# 00A-094.net
KiCad netlist of a schematic drawn in EAGLE
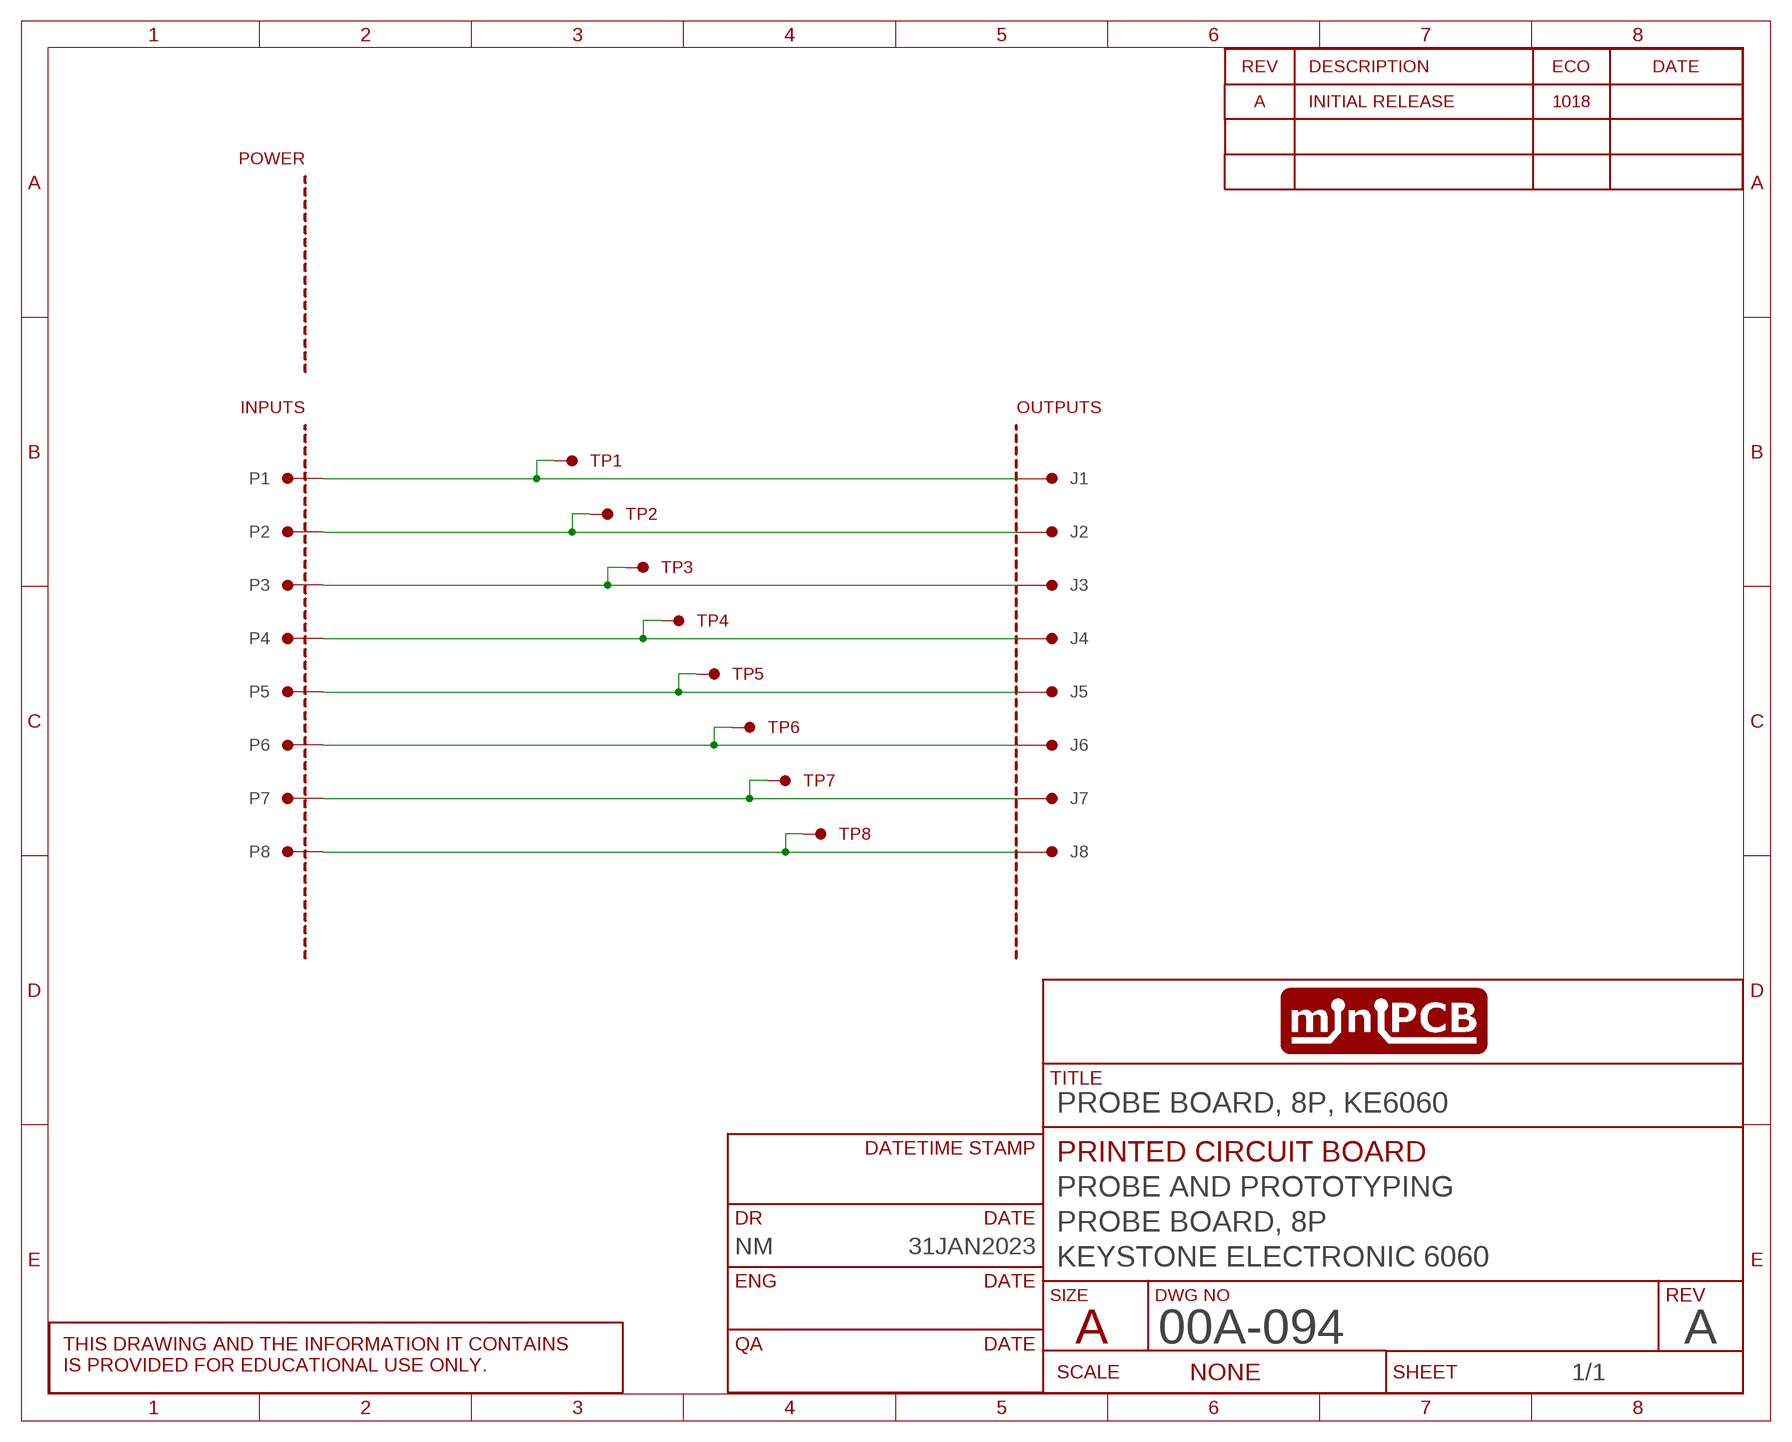
[diagram p0: schematic, sheet 1]

(export (version "E")
  (design (tool "Eeschema 10.0.6"))
  (components
    (comp (ref "J1")
      (value "PINS_1KE6060")
      (footprint "eagle-import:PINS_1_KE6060")
      (libsource (lib "eagle-import") (part "PINS_1KE6060"))
    )
    (comp (ref "J2")
      (value "PINS_1KE6060")
      (footprint "eagle-import:PINS_1_KE6060")
      (libsource (lib "eagle-import") (part "PINS_1KE6060"))
    )
    (comp (ref "J3")
      (value "PINS_1KE6060")
      (footprint "eagle-import:PINS_1_KE6060")
      (libsource (lib "eagle-import") (part "PINS_1KE6060"))
    )
    (comp (ref "J4")
      (value "PINS_1KE6060")
      (footprint "eagle-import:PINS_1_KE6060")
      (libsource (lib "eagle-import") (part "PINS_1KE6060"))
    )
    (comp (ref "J5")
      (value "PINS_1KE6060")
      (footprint "eagle-import:PINS_1_KE6060")
      (libsource (lib "eagle-import") (part "PINS_1KE6060"))
    )
    (comp (ref "J6")
      (value "PINS_1KE6060")
      (footprint "eagle-import:PINS_1_KE6060")
      (libsource (lib "eagle-import") (part "PINS_1KE6060"))
    )
    (comp (ref "J7")
      (value "PINS_1KE6060")
      (footprint "eagle-import:PINS_1_KE6060")
      (libsource (lib "eagle-import") (part "PINS_1KE6060"))
    )
    (comp (ref "J8")
      (value "PINS_1KE6060")
      (footprint "eagle-import:PINS_1_KE6060")
      (libsource (lib "eagle-import") (part "PINS_1KE6060"))
    )
    (comp (ref "P1")
      (value "PINS_124AWG-NOTEXT")
      (footprint "eagle-import:PINS_1_1MM-NOTEXT")
      (libsource (lib "eagle-import") (part "PINS_124AWG-NOTEXT"))
    )
    (comp (ref "P2")
      (value "PINS_124AWG-NOTEXT")
      (footprint "eagle-import:PINS_1_1MM-NOTEXT")
      (libsource (lib "eagle-import") (part "PINS_124AWG-NOTEXT"))
    )
    (comp (ref "P3")
      (value "PINS_124AWG-NOTEXT")
      (footprint "eagle-import:PINS_1_1MM-NOTEXT")
      (libsource (lib "eagle-import") (part "PINS_124AWG-NOTEXT"))
    )
    (comp (ref "P4")
      (value "PINS_124AWG-NOTEXT")
      (footprint "eagle-import:PINS_1_1MM-NOTEXT")
      (libsource (lib "eagle-import") (part "PINS_124AWG-NOTEXT"))
    )
    (comp (ref "P5")
      (value "PINS_124AWG-NOTEXT")
      (footprint "eagle-import:PINS_1_1MM-NOTEXT")
      (libsource (lib "eagle-import") (part "PINS_124AWG-NOTEXT"))
    )
    (comp (ref "P6")
      (value "PINS_124AWG-NOTEXT")
      (footprint "eagle-import:PINS_1_1MM-NOTEXT")
      (libsource (lib "eagle-import") (part "PINS_124AWG-NOTEXT"))
    )
    (comp (ref "P7")
      (value "PINS_124AWG-NOTEXT")
      (footprint "eagle-import:PINS_1_1MM-NOTEXT")
      (libsource (lib "eagle-import") (part "PINS_124AWG-NOTEXT"))
    )
    (comp (ref "P8")
      (value "PINS_124AWG-NOTEXT")
      (footprint "eagle-import:PINS_1_1MM-NOTEXT")
      (libsource (lib "eagle-import") (part "PINS_124AWG-NOTEXT"))
    )
    (comp (ref "PCB1")
      (value "MINIPCB_0P00A-20X100")
      (footprint "eagle-import:MINIPCB_00A_20X100")
      (fields (field (name "PART_NUMBER") "00A-094-A"))
      (libsource (lib "eagle-import") (part "MINIPCB_0P00A-20X100"))
    )
    (comp (ref "TP1")
      (value "TESTPOINTKE5000-SMTEXT")
      (footprint "eagle-import:PINS_1_TESTPOINT_KE5000_NOTEXT")
      (libsource (lib "eagle-import") (part "TESTPOINTKE5000-SMTEXT"))
    )
    (comp (ref "TP2")
      (value "TESTPOINTKE5000-SMTEXT")
      (footprint "eagle-import:PINS_1_TESTPOINT_KE5000_NOTEXT")
      (libsource (lib "eagle-import") (part "TESTPOINTKE5000-SMTEXT"))
    )
    (comp (ref "TP3")
      (value "TESTPOINTKE5000-SMTEXT")
      (footprint "eagle-import:PINS_1_TESTPOINT_KE5000_NOTEXT")
      (libsource (lib "eagle-import") (part "TESTPOINTKE5000-SMTEXT"))
    )
    (comp (ref "TP4")
      (value "TESTPOINTKE5000-SMTEXT")
      (footprint "eagle-import:PINS_1_TESTPOINT_KE5000_NOTEXT")
      (libsource (lib "eagle-import") (part "TESTPOINTKE5000-SMTEXT"))
    )
    (comp (ref "TP5")
      (value "TESTPOINTKE5000-SMTEXT")
      (footprint "eagle-import:PINS_1_TESTPOINT_KE5000_NOTEXT")
      (libsource (lib "eagle-import") (part "TESTPOINTKE5000-SMTEXT"))
    )
    (comp (ref "TP6")
      (value "TESTPOINTKE5000-SMTEXT")
      (footprint "eagle-import:PINS_1_TESTPOINT_KE5000_NOTEXT")
      (libsource (lib "eagle-import") (part "TESTPOINTKE5000-SMTEXT"))
    )
    (comp (ref "TP7")
      (value "TESTPOINTKE5000-SMTEXT")
      (footprint "eagle-import:PINS_1_TESTPOINT_KE5000_NOTEXT")
      (libsource (lib "eagle-import") (part "TESTPOINTKE5000-SMTEXT"))
    )
    (comp (ref "TP8")
      (value "TESTPOINTKE5000-SMTEXT")
      (footprint "eagle-import:PINS_1_TESTPOINT_KE5000_NOTEXT")
      (libsource (lib "eagle-import") (part "TESTPOINTKE5000-SMTEXT"))
    )
  )
  (nets
    (net (code "1") (name "Net-(J1-1-Pad2)") (class "Default")
      (node (ref "J1") (pin "1") (pinfunction "1_1") (pintype "bidirectional"))
      (node (ref "J1") (pin "2") (pinfunction "1_2") (pintype "bidirectional"))
      (node (ref "P1") (pin "1") (pinfunction "1_1") (pintype "bidirectional"))
      (node (ref "P1") (pin "2") (pinfunction "1_2") (pintype "bidirectional"))
      (node (ref "TP1") (pin "1") (pinfunction "1_1") (pintype "bidirectional"))
    )
    (net (code "2") (name "Net-(J2-1-Pad2)") (class "Default")
      (node (ref "J2") (pin "1") (pinfunction "1_1") (pintype "bidirectional"))
      (node (ref "J2") (pin "2") (pinfunction "1_2") (pintype "bidirectional"))
      (node (ref "P2") (pin "1") (pinfunction "1_1") (pintype "bidirectional"))
      (node (ref "P2") (pin "2") (pinfunction "1_2") (pintype "bidirectional"))
      (node (ref "TP2") (pin "1") (pinfunction "1_1") (pintype "bidirectional"))
    )
    (net (code "3") (name "Net-(J3-1-Pad2)") (class "Default")
      (node (ref "J3") (pin "1") (pinfunction "1_1") (pintype "bidirectional"))
      (node (ref "J3") (pin "2") (pinfunction "1_2") (pintype "bidirectional"))
      (node (ref "P3") (pin "1") (pinfunction "1_1") (pintype "bidirectional"))
      (node (ref "P3") (pin "2") (pinfunction "1_2") (pintype "bidirectional"))
      (node (ref "TP3") (pin "1") (pinfunction "1_1") (pintype "bidirectional"))
    )
    (net (code "4") (name "Net-(J4-1-Pad2)") (class "Default")
      (node (ref "J4") (pin "1") (pinfunction "1_1") (pintype "bidirectional"))
      (node (ref "J4") (pin "2") (pinfunction "1_2") (pintype "bidirectional"))
      (node (ref "P4") (pin "1") (pinfunction "1_1") (pintype "bidirectional"))
      (node (ref "P4") (pin "2") (pinfunction "1_2") (pintype "bidirectional"))
      (node (ref "TP4") (pin "1") (pinfunction "1_1") (pintype "bidirectional"))
    )
    (net (code "5") (name "Net-(J5-1-Pad2)") (class "Default")
      (node (ref "J5") (pin "1") (pinfunction "1_1") (pintype "bidirectional"))
      (node (ref "J5") (pin "2") (pinfunction "1_2") (pintype "bidirectional"))
      (node (ref "P5") (pin "1") (pinfunction "1_1") (pintype "bidirectional"))
      (node (ref "P5") (pin "2") (pinfunction "1_2") (pintype "bidirectional"))
      (node (ref "TP5") (pin "1") (pinfunction "1_1") (pintype "bidirectional"))
    )
    (net (code "6") (name "Net-(J6-1-Pad2)") (class "Default")
      (node (ref "J6") (pin "1") (pinfunction "1_1") (pintype "bidirectional"))
      (node (ref "J6") (pin "2") (pinfunction "1_2") (pintype "bidirectional"))
      (node (ref "P6") (pin "1") (pinfunction "1_1") (pintype "bidirectional"))
      (node (ref "P6") (pin "2") (pinfunction "1_2") (pintype "bidirectional"))
      (node (ref "TP6") (pin "1") (pinfunction "1_1") (pintype "bidirectional"))
    )
    (net (code "7") (name "Net-(J7-1-Pad2)") (class "Default")
      (node (ref "J7") (pin "1") (pinfunction "1_1") (pintype "bidirectional"))
      (node (ref "J7") (pin "2") (pinfunction "1_2") (pintype "bidirectional"))
      (node (ref "P7") (pin "1") (pinfunction "1_1") (pintype "bidirectional"))
      (node (ref "P7") (pin "2") (pinfunction "1_2") (pintype "bidirectional"))
      (node (ref "TP7") (pin "1") (pinfunction "1_1") (pintype "bidirectional"))
    )
    (net (code "8") (name "Net-(J8-1-Pad2)") (class "Default")
      (node (ref "J8") (pin "1") (pinfunction "1_1") (pintype "bidirectional"))
      (node (ref "J8") (pin "2") (pinfunction "1_2") (pintype "bidirectional"))
      (node (ref "P8") (pin "1") (pinfunction "1_1") (pintype "bidirectional"))
      (node (ref "P8") (pin "2") (pinfunction "1_2") (pintype "bidirectional"))
      (node (ref "TP8") (pin "1") (pinfunction "1_1") (pintype "bidirectional"))
    )
  )
)
